# ee242a-lab4-amp2.net
KiCad netlist of a schematic drawn in EAGLE
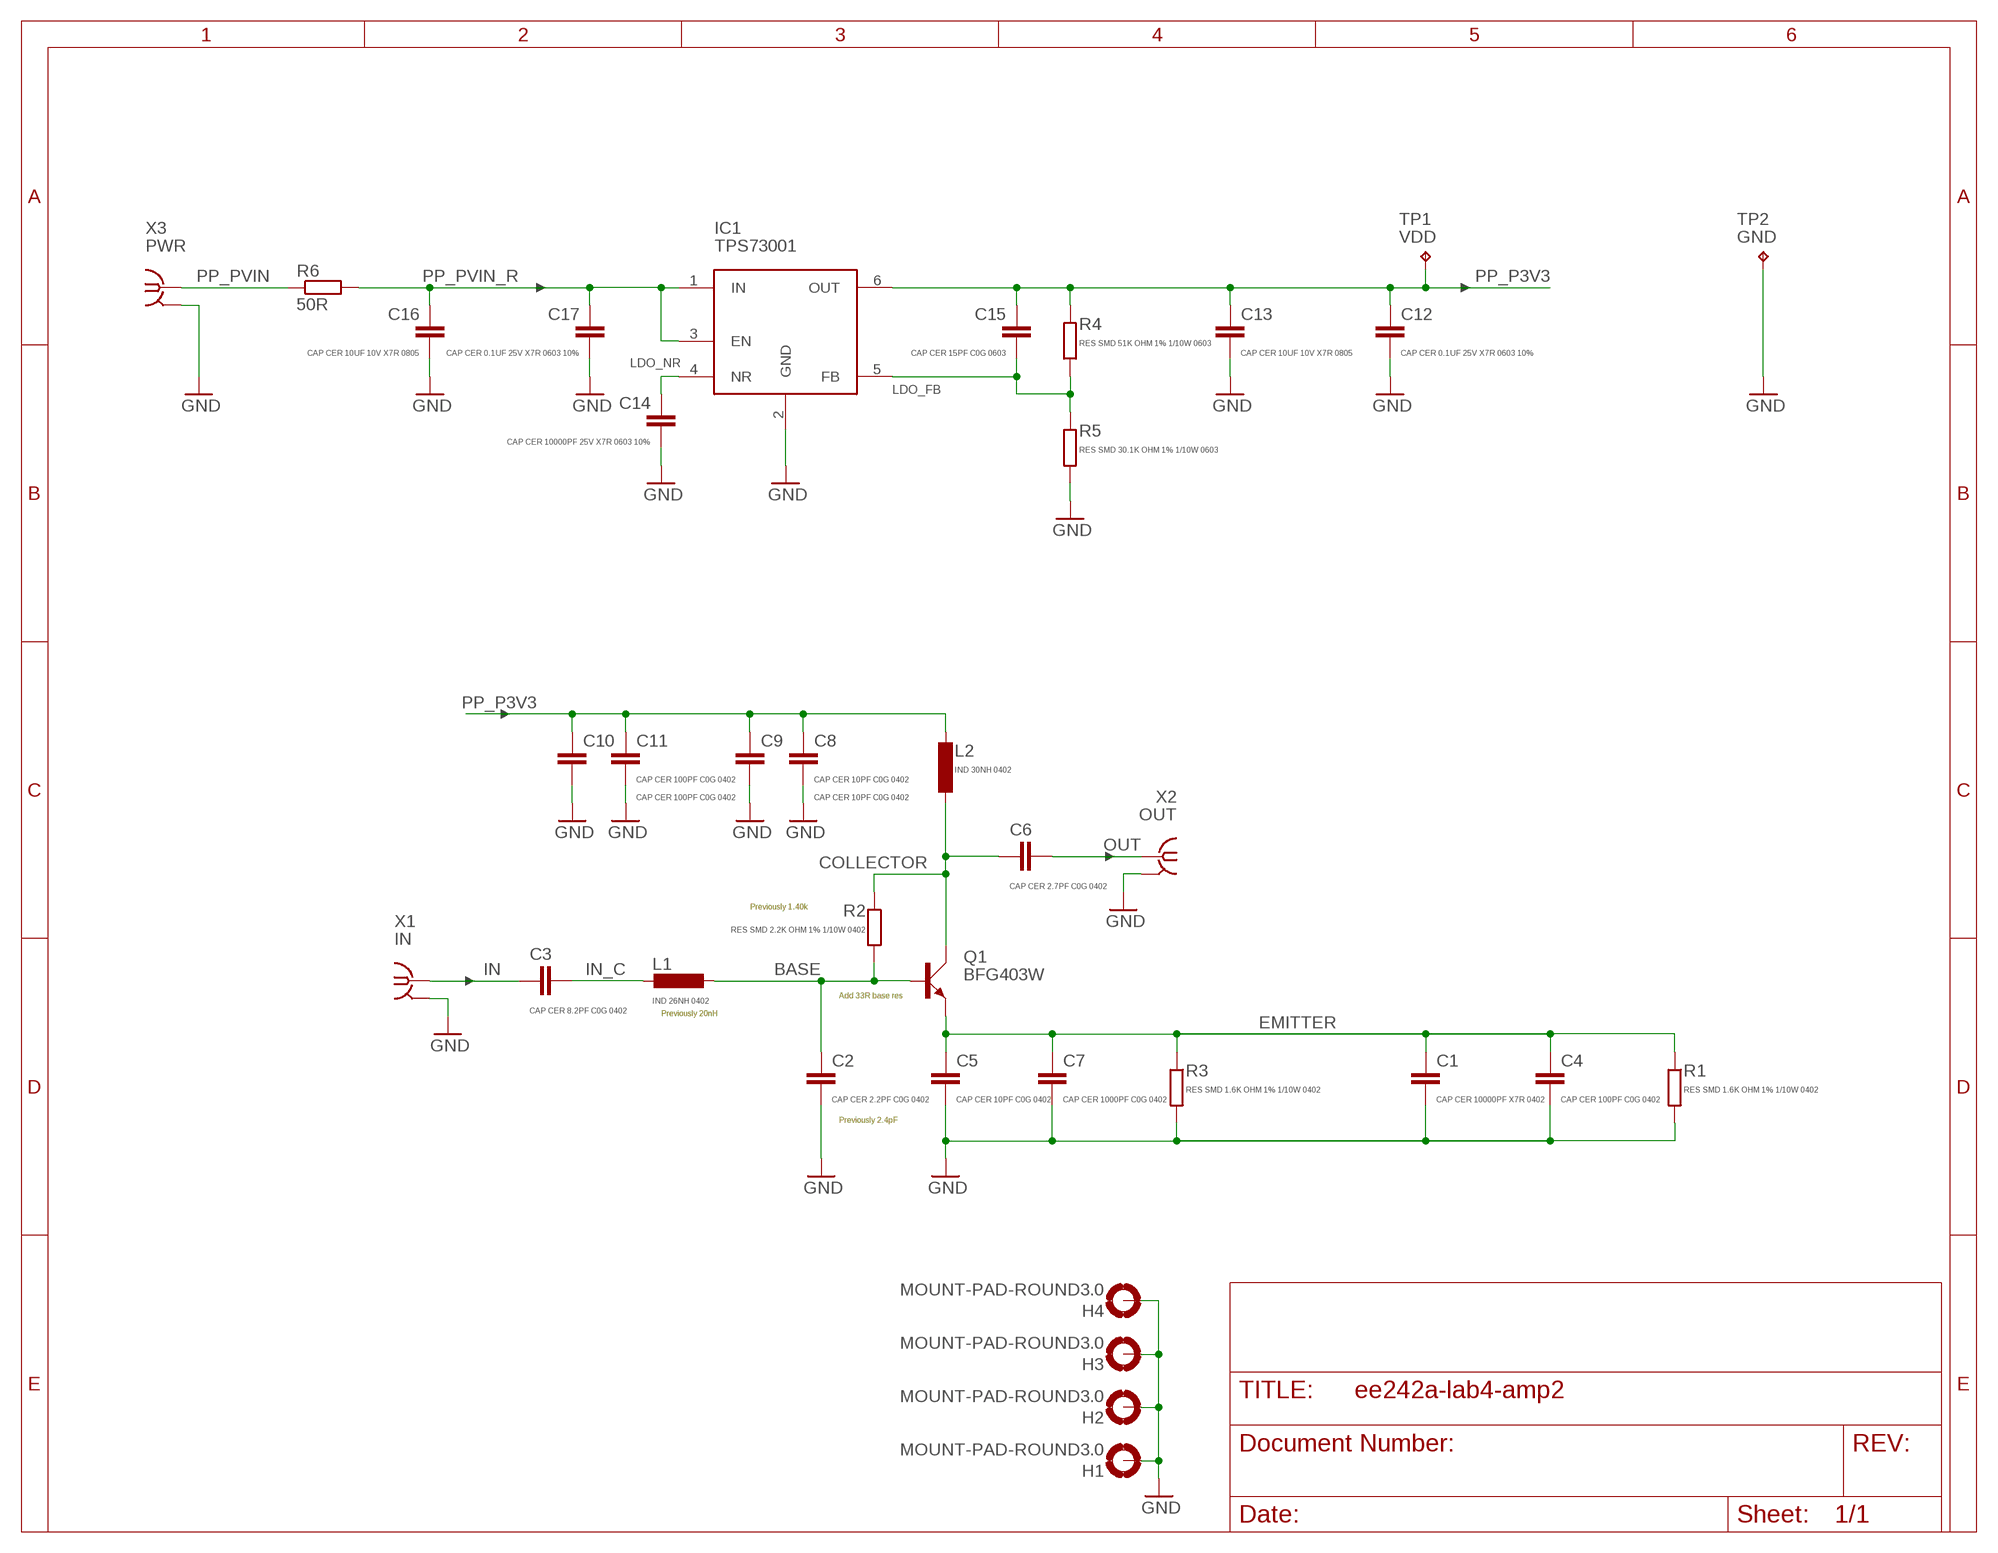
[diagram p0: schematic, sheet 1]

(export (version "E")
  (design (tool "Eeschema 10.0.6"))
  (components
    (comp (ref "C1")
      (value "CAP CER 10000PF X7R 0402")
      (footprint "eagle-import:C0402")
      (libsource (lib "eagle-import") (part "rcl-modified-footprints_C-EUC0402"))
    )
    (comp (ref "C2")
      (value "CAP CER 2.2PF C0G 0402")
      (footprint "eagle-import:C0402")
      (libsource (lib "eagle-import") (part "rcl-modified-footprints_C-EUC0402"))
    )
    (comp (ref "C3")
      (value "CAP CER 8.2PF C0G 0402")
      (footprint "eagle-import:C0402")
      (libsource (lib "eagle-import") (part "rcl-modified-footprints_C-EUC0402"))
    )
    (comp (ref "C4")
      (value "CAP CER 100PF C0G 0402")
      (footprint "eagle-import:C0402")
      (libsource (lib "eagle-import") (part "rcl-modified-footprints_C-EUC0402"))
    )
    (comp (ref "C5")
      (value "CAP CER 10PF C0G 0402")
      (footprint "eagle-import:C0402")
      (libsource (lib "eagle-import") (part "rcl-modified-footprints_C-EUC0402"))
    )
    (comp (ref "C6")
      (value "CAP CER 2.7PF C0G 0402")
      (footprint "eagle-import:C0402")
      (libsource (lib "eagle-import") (part "rcl-modified-footprints_C-EUC0402"))
    )
    (comp (ref "C7")
      (value "CAP CER 1000PF C0G 0402")
      (footprint "eagle-import:C0402")
      (libsource (lib "eagle-import") (part "rcl-modified-footprints_C-EUC0402"))
    )
    (comp (ref "C8")
      (value "CAP CER 10PF C0G 0402")
      (footprint "eagle-import:C0402")
      (libsource (lib "eagle-import") (part "rcl-modified-footprints_C-EUC0402"))
    )
    (comp (ref "C9")
      (value "CAP CER 10PF C0G 0402")
      (footprint "eagle-import:C0402")
      (libsource (lib "eagle-import") (part "rcl-modified-footprints_C-EUC0402"))
    )
    (comp (ref "C10")
      (value "CAP CER 100PF C0G 0402")
      (footprint "eagle-import:C0402")
      (libsource (lib "eagle-import") (part "rcl-modified-footprints_C-EUC0402"))
    )
    (comp (ref "C11")
      (value "CAP CER 100PF C0G 0402")
      (footprint "eagle-import:C0402")
      (libsource (lib "eagle-import") (part "rcl-modified-footprints_C-EUC0402"))
    )
    (comp (ref "C12")
      (value "CAP CER 0.1UF 25V X7R 0603 10%")
      (footprint "eagle-import:C0603")
      (libsource (lib "eagle-import") (part "rcl-modified-footprints_C-EUC0603"))
    )
    (comp (ref "C13")
      (value "CAP CER 10UF 10V X7R 0805")
      (footprint "eagle-import:C0805")
      (libsource (lib "eagle-import") (part "C-EUC0805"))
    )
    (comp (ref "C14")
      (value "CAP CER 10000PF 25V X7R 0603 10%")
      (footprint "eagle-import:C0603")
      (libsource (lib "eagle-import") (part "rcl-modified-footprints_C-EUC0603"))
    )
    (comp (ref "C15")
      (value "CAP CER 15PF C0G 0603")
      (footprint "eagle-import:C0603")
      (libsource (lib "eagle-import") (part "rcl-modified-footprints_C-EUC0603"))
    )
    (comp (ref "C16")
      (value "CAP CER 10UF 10V X7R 0805")
      (footprint "eagle-import:C0805")
      (libsource (lib "eagle-import") (part "C-EUC0805"))
    )
    (comp (ref "C17")
      (value "CAP CER 0.1UF 25V X7R 0603 10%")
      (footprint "eagle-import:C0603")
      (libsource (lib "eagle-import") (part "rcl-modified-footprints_C-EUC0603"))
    )
    (comp (ref "H1")
      (value "MOUNT-PAD-ROUND3.0")
      (footprint "eagle-import:3,0-PAD")
      (libsource (lib "eagle-import") (part "MOUNT-PAD-ROUND3.0"))
    )
    (comp (ref "H2")
      (value "MOUNT-PAD-ROUND3.0")
      (footprint "eagle-import:3,0-PAD")
      (libsource (lib "eagle-import") (part "MOUNT-PAD-ROUND3.0"))
    )
    (comp (ref "H3")
      (value "MOUNT-PAD-ROUND3.0")
      (footprint "eagle-import:3,0-PAD")
      (libsource (lib "eagle-import") (part "MOUNT-PAD-ROUND3.0"))
    )
    (comp (ref "H4")
      (value "MOUNT-PAD-ROUND3.0")
      (footprint "eagle-import:3,0-PAD")
      (libsource (lib "eagle-import") (part "MOUNT-PAD-ROUND3.0"))
    )
    (comp (ref "IC1")
      (value "TPS73001")
      (footprint "eagle-import:SOT23-6L")
      (libsource (lib "eagle-import") (part "TPS73001"))
    )
    (comp (ref "L1")
      (value "IND 26NH 0402")
      (footprint "eagle-import:R0402")
      (libsource (lib "eagle-import") (part "L-EU0402"))
    )
    (comp (ref "L2")
      (value "IND 30NH 0402")
      (footprint "eagle-import:R0402")
      (libsource (lib "eagle-import") (part "L-EU0402"))
    )
    (comp (ref "Q1")
      (value "BFG403W")
      (footprint "eagle-import:SOT343R")
      (libsource (lib "eagle-import") (part "BFG403W"))
    )
    (comp (ref "R1")
      (value "RES SMD 1.6K OHM 1% 1/10W 0402")
      (footprint "eagle-import:R0402")
      (libsource (lib "eagle-import") (part "R-EU_R0402"))
    )
    (comp (ref "R2")
      (value "RES SMD 2.2K OHM 1% 1/10W 0402")
      (footprint "eagle-import:R0402")
      (libsource (lib "eagle-import") (part "R-EU_R0402"))
    )
    (comp (ref "R3")
      (value "RES SMD 1.6K OHM 1% 1/10W 0402")
      (footprint "eagle-import:R0402")
      (libsource (lib "eagle-import") (part "R-EU_R0402"))
    )
    (comp (ref "R4")
      (value "RES SMD 51K OHM 1% 1/10W 0603")
      (footprint "eagle-import:R0603")
      (libsource (lib "eagle-import") (part "R-EU_R0603"))
    )
    (comp (ref "R5")
      (value "RES SMD 30.1K OHM 1% 1/10W 0603")
      (footprint "eagle-import:R0603")
      (libsource (lib "eagle-import") (part "R-EU_R0603"))
    )
    (comp (ref "R6")
      (value "50R")
      (footprint "eagle-import:R0805")
      (libsource (lib "eagle-import") (part "R-EU_R0805"))
    )
    (comp (ref "TP1")
      (value "VDD")
      (footprint "eagle-import:KEYSTONE_5000_MINIATURE")
      (libsource (lib "eagle-import") (part "KEYSTONE_5000"))
    )
    (comp (ref "TP2")
      (value "GND")
      (footprint "eagle-import:KEYSTONE_5000_MINIATURE")
      (libsource (lib "eagle-import") (part "KEYSTONE_5000"))
    )
    (comp (ref "X1")
      (value "IN")
      (footprint "eagle-import:J502-ND-142-0701-881_886")
      (fields (field (name "MF") "JOHNSON COMPONENTS") (field (name "MPN") "142-0701-881"))
      (libsource (lib "eagle-import") (part "SMA-142-0701-881/886"))
    )
    (comp (ref "X2")
      (value "OUT")
      (footprint "eagle-import:J502-ND-142-0701-881_886")
      (fields (field (name "MF") "JOHNSON COMPONENTS") (field (name "MPN") "142-0701-881"))
      (libsource (lib "eagle-import") (part "SMA-142-0701-881/886"))
    )
    (comp (ref "X3")
      (value "PWR")
      (footprint "eagle-import:J502-ND-142-0701-881_886")
      (fields (field (name "MF") "JOHNSON COMPONENTS") (field (name "MPN") "142-0701-881"))
      (libsource (lib "eagle-import") (part "SMA-142-0701-881/886"))
    )
  )
  (nets
    (net (code "1") (name "/BASE") (class "Default")
      (node (ref "C2") (pin "1") (pinfunction "1_1") (pintype "passive"))
      (node (ref "L1") (pin "2") (pinfunction "2_2") (pintype "passive"))
      (node (ref "Q1") (pin "2") (pinfunction "B_2") (pintype "passive"))
      (node (ref "R2") (pin "2") (pinfunction "2_2") (pintype "passive"))
    )
    (net (code "2") (name "/COLLECTOR") (class "Default")
      (node (ref "C6") (pin "1") (pinfunction "1_1") (pintype "passive"))
      (node (ref "L2") (pin "2") (pinfunction "2_2") (pintype "passive"))
      (node (ref "Q1") (pin "4") (pinfunction "C_4") (pintype "passive"))
      (node (ref "R2") (pin "1") (pinfunction "1_1") (pintype "passive"))
    )
    (net (code "3") (name "/EMITTER") (class "Default")
      (node (ref "C1") (pin "1") (pinfunction "1_1") (pintype "passive"))
      (node (ref "C4") (pin "1") (pinfunction "1_1") (pintype "passive"))
      (node (ref "C5") (pin "1") (pinfunction "1_1") (pintype "passive"))
      (node (ref "C7") (pin "1") (pinfunction "1_1") (pintype "passive"))
      (node (ref "Q1") (pin "1") (pinfunction "E_1") (pintype "passive"))
      (node (ref "Q1") (pin "3") (pinfunction "E_3") (pintype "passive"))
      (node (ref "R1") (pin "1") (pinfunction "1_1") (pintype "passive"))
      (node (ref "R3") (pin "1") (pinfunction "1_1") (pintype "passive"))
    )
    (net (code "4") (name "/IN") (class "Default")
      (node (ref "C3") (pin "1") (pinfunction "1_1") (pintype "passive"))
      (node (ref "X1") (pin "1") (pinfunction "1_1") (pintype "passive"))
    )
    (net (code "5") (name "/IN_C") (class "Default")
      (node (ref "C3") (pin "2") (pinfunction "2_2") (pintype "passive"))
      (node (ref "L1") (pin "1") (pinfunction "1_1") (pintype "passive"))
    )
    (net (code "6") (name "/LDO_FB") (class "Default")
      (node (ref "C15") (pin "2") (pinfunction "2_2") (pintype "passive"))
      (node (ref "IC1") (pin "5") (pinfunction "FB_5") (pintype "bidirectional"))
      (node (ref "R4") (pin "1") (pinfunction "1_1") (pintype "passive"))
      (node (ref "R5") (pin "1") (pinfunction "1_1") (pintype "passive"))
    )
    (net (code "7") (name "/LDO_NR") (class "Default")
      (node (ref "C14") (pin "1") (pinfunction "1_1") (pintype "passive"))
      (node (ref "IC1") (pin "4") (pinfunction "NR_4") (pintype "bidirectional"))
    )
    (net (code "8") (name "/OUT") (class "Default")
      (node (ref "C6") (pin "2") (pinfunction "2_2") (pintype "passive"))
      (node (ref "X2") (pin "1") (pinfunction "1_1") (pintype "passive"))
    )
    (net (code "9") (name "/PP_P3V3") (class "Default")
      (node (ref "C10") (pin "1") (pinfunction "1_1") (pintype "passive"))
      (node (ref "C11") (pin "1") (pinfunction "1_1") (pintype "passive"))
      (node (ref "C12") (pin "1") (pinfunction "1_1") (pintype "passive"))
      (node (ref "C13") (pin "1") (pinfunction "1_1") (pintype "passive"))
      (node (ref "C15") (pin "1") (pinfunction "1_1") (pintype "passive"))
      (node (ref "C8") (pin "1") (pinfunction "1_1") (pintype "passive"))
      (node (ref "C9") (pin "1") (pinfunction "1_1") (pintype "passive"))
      (node (ref "IC1") (pin "6") (pinfunction "OUT_6") (pintype "bidirectional"))
      (node (ref "L2") (pin "1") (pinfunction "1_1") (pintype "passive"))
      (node (ref "R4") (pin "2") (pinfunction "2_2") (pintype "passive"))
      (node (ref "TP1") (pin "P$1") (pinfunction "P$1_P$1") (pintype "bidirectional"))
    )
    (net (code "10") (name "/PP_PVIN") (class "Default")
      (node (ref "R6") (pin "1") (pinfunction "1_1") (pintype "passive"))
      (node (ref "X3") (pin "1") (pinfunction "1_1") (pintype "passive"))
    )
    (net (code "11") (name "/PP_PVIN_R") (class "Default")
      (node (ref "C16") (pin "1") (pinfunction "1_1") (pintype "passive"))
      (node (ref "C17") (pin "1") (pinfunction "1_1") (pintype "passive"))
      (node (ref "IC1") (pin "1") (pinfunction "IN_1") (pintype "bidirectional"))
      (node (ref "IC1") (pin "3") (pinfunction "EN_3") (pintype "bidirectional"))
      (node (ref "R6") (pin "2") (pinfunction "2_2") (pintype "passive"))
    )
    (net (code "12") (name "GND") (class "Default")
      (node (ref "C1") (pin "2") (pinfunction "2_2") (pintype "passive"))
      (node (ref "C10") (pin "2") (pinfunction "2_2") (pintype "passive"))
      (node (ref "C11") (pin "2") (pinfunction "2_2") (pintype "passive"))
      (node (ref "C12") (pin "2") (pinfunction "2_2") (pintype "passive"))
      (node (ref "C13") (pin "2") (pinfunction "2_2") (pintype "passive"))
      (node (ref "C14") (pin "2") (pinfunction "2_2") (pintype "passive"))
      (node (ref "C16") (pin "2") (pinfunction "2_2") (pintype "passive"))
      (node (ref "C17") (pin "2") (pinfunction "2_2") (pintype "passive"))
      (node (ref "C2") (pin "2") (pinfunction "2_2") (pintype "passive"))
      (node (ref "C4") (pin "2") (pinfunction "2_2") (pintype "passive"))
      (node (ref "C5") (pin "2") (pinfunction "2_2") (pintype "passive"))
      (node (ref "C7") (pin "2") (pinfunction "2_2") (pintype "passive"))
      (node (ref "C8") (pin "2") (pinfunction "2_2") (pintype "passive"))
      (node (ref "C9") (pin "2") (pinfunction "2_2") (pintype "passive"))
      (node (ref "H1") (pin "B3,0") (pinfunction "MOUNT_B3,0") (pintype "passive"))
      (node (ref "H2") (pin "B3,0") (pinfunction "MOUNT_B3,0") (pintype "passive"))
      (node (ref "H3") (pin "B3,0") (pinfunction "MOUNT_B3,0") (pintype "passive"))
      (node (ref "H4") (pin "B3,0") (pinfunction "MOUNT_B3,0") (pintype "passive"))
      (node (ref "IC1") (pin "2") (pinfunction "GND_2") (pintype "bidirectional"))
      (node (ref "R1") (pin "2") (pinfunction "2_2") (pintype "passive"))
      (node (ref "R3") (pin "2") (pinfunction "2_2") (pintype "passive"))
      (node (ref "R5") (pin "2") (pinfunction "2_2") (pintype "passive"))
      (node (ref "TP2") (pin "P$1") (pinfunction "P$1_P$1") (pintype "bidirectional"))
      (node (ref "X1") (pin "G@1") (pinfunction "GND_G@1") (pintype "power_in"))
      (node (ref "X2") (pin "G@1") (pinfunction "GND_G@1") (pintype "power_in"))
      (node (ref "X3") (pin "G@1") (pinfunction "GND_G@1") (pintype "power_in"))
    )
  )
)
